# 10-Programmer.net
KiCad netlist of a schematic drawn in Altium Designer
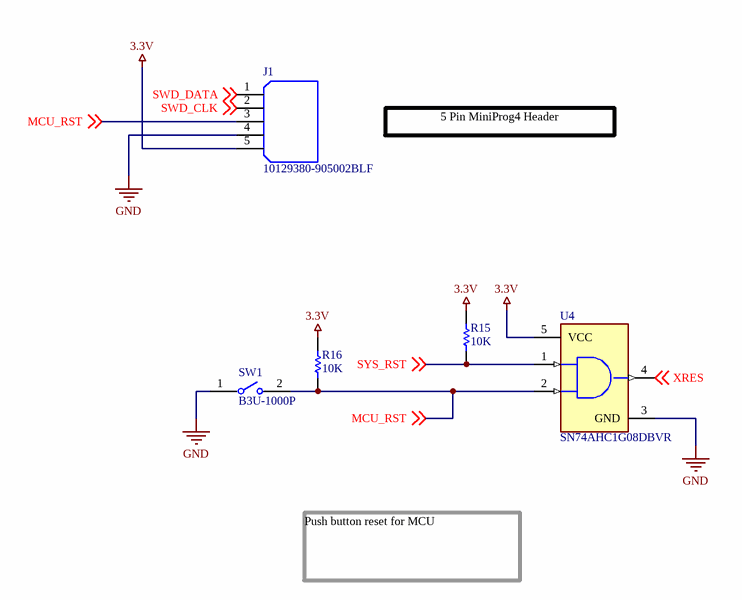
[diagram p0: 10-Programmer.SchDoc]

(export (version "E")
  (design (tool "Eeschema 10.0.6"))
  (components
    (comp (ref "J1")
      (value "10129380-905002BLF")
      (footprint "AMPHENOL_10129380-905002BLF")
      (description "Conn Unshrouded Header HDR 5 POS 2.54mm Solder ST SMD Poly Bag")
      (fields (field (name "MF") "AMPHENOL ICC / FCI"))
      (libsource (lib "ece353-2022") (part "10129380-905002BLF"))
    )
    (comp (ref "R15")
      (value "RC1206FR-0710KL")
      (footprint "RESC3116X65X40ML10T20")
      (description "Chip Resistor, 10 KOhm, +/- 1%, 0.25 W, -55 to 155 degC, 1206 (3216 Metric), RoHS, Tape and Reel")
      (fields
        (field (name "TOLERANCE") "1%")
        (field (name "RESISTANCE") "10K")
        (field (name "MANUFACTURER") "Yageo")
      )
      (libsource (lib "Altium Content Vault") (part "RES-2"))
    )
    (comp (ref "R16")
      (value "RC1206FR-0710KL")
      (footprint "RESC3116X65X40ML10T20")
      (description "Chip Resistor, 10 KOhm, +/- 1%, 0.25 W, -55 to 155 degC, 1206 (3216 Metric), RoHS, Tape and Reel")
      (fields
        (field (name "TOLERANCE") "1%")
        (field (name "RESISTANCE") "10K")
        (field (name "MANUFACTURER") "Yageo")
      )
      (libsource (lib "Altium Content Vault") (part "RES-2"))
    )
    (comp (ref "SW1")
      (value "B3U-1000P")
      (footprint "FP-B3U-1000P-MFG")
      (description "SWITCH TACTILE SPST-NO 0.05A 12V")
      (fields (field (name "MANUFACTURER") "Omron"))
      (libsource (lib "Altium Content Vault") (part "ae622034201233ca1abcedc05908f33"))
    )
    (comp (ref "U4")
      (value "SN74AHC1G08DBVR")
      (footprint "FP-DBV0005A-MFG")
      (description "IC GATE AND 1CH 2-INP SOT23-5")
      (fields
        (field (name "MANUFACTURER") "Texas Instruments")
        (field (name "OCTOPART") "https://octopart.com/sn74ahc1g08dbvr-texas+instruments-464404")
      )
      (libsource (lib "Altium Content Vault") (part "7d5472fad8fac2169e6b8dda8b756c7"))
    )
  )
  (nets
    (net (code "1") (name "3.3V") (class "Default")
      (node (ref "J1") (pin "5") (pinfunction "5_5") (pintype "passive"))
      (node (ref "R15") (pin "2") (pinfunction "2_2") (pintype "passive"))
      (node (ref "R16") (pin "2") (pinfunction "2_2") (pintype "passive"))
      (node (ref "U4") (pin "5") (pinfunction "VCC_5") (pintype "power_in"))
    )
    (net (code "2") (name "GND") (class "Default")
      (node (ref "J1") (pin "4") (pinfunction "4_4") (pintype "passive"))
      (node (ref "SW1") (pin "1") (pinfunction "1_1") (pintype "passive"))
      (node (ref "U4") (pin "3") (pinfunction "GND_3") (pintype "power_in"))
    )
    (net (code "3") (name "MCU_RST") (class "Default")
      (node (ref "J1") (pin "3") (pinfunction "3_3") (pintype "passive"))
      (node (ref "R16") (pin "1") (pinfunction "1_1") (pintype "passive"))
      (node (ref "SW1") (pin "2") (pinfunction "2_2") (pintype "passive"))
      (node (ref "U4") (pin "2") (pinfunction "B_2") (pintype "input"))
    )
    (net (code "4") (name "SWD_CLK") (class "Default")
      (node (ref "J1") (pin "2") (pinfunction "2_2") (pintype "passive"))
    )
    (net (code "5") (name "SWD_DATA") (class "Default")
      (node (ref "J1") (pin "1") (pinfunction "1_1") (pintype "passive"))
    )
    (net (code "6") (name "SYS_RST") (class "Default")
      (node (ref "R15") (pin "1") (pinfunction "1_1") (pintype "passive"))
      (node (ref "U4") (pin "1") (pinfunction "A_1") (pintype "input"))
    )
    (net (code "7") (name "XRES") (class "Default")
      (node (ref "U4") (pin "4") (pinfunction "Y_4") (pintype "output"))
    )
  )
)
